# AirSensor_LoRA.net
KiCad netlist of a schematic drawn in EAGLE
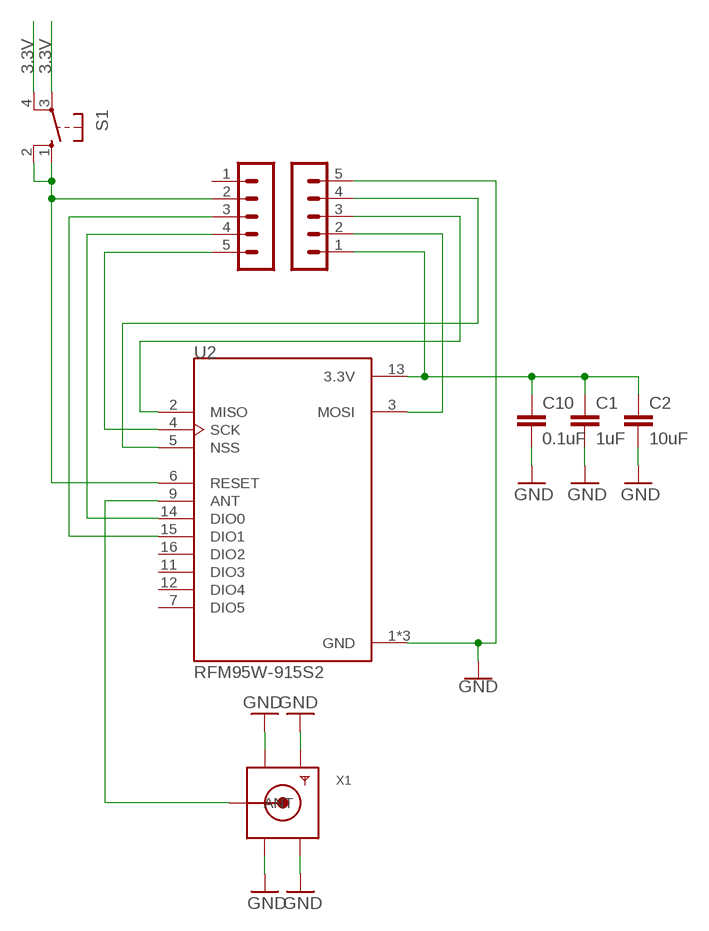
[diagram p0: schematic, sheet 1]

(export (version "E")
  (design (tool "Eeschema 10.0.6"))
  (components
    (comp (ref "C1")
      (value "1uF")
      (footprint "eagle-import:0805")
      (libsource (lib "eagle-import") (part "1.0UF-0805-25V-10%"))
    )
    (comp (ref "C2")
      (value "10uF")
      (footprint "eagle-import:0805")
      (libsource (lib "eagle-import") (part "1.0UF-0805-25V-10%"))
    )
    (comp (ref "C10")
      (value "0.1uF")
      (footprint "eagle-import:0805")
      (libsource (lib "eagle-import") (part "1.0UF-0805-25V-10%"))
    )
    (comp (ref "RFM95W_1")
      (value "LoRa_1")
      (footprint "eagle-import:MA05-1")
      (libsource (lib "eagle-import") (part "MA05-1"))
    )
    (comp (ref "RFM95W_2")
      (value "LoRa_2")
      (footprint "eagle-import:MA05-1")
      (libsource (lib "eagle-import") (part "MA05-1"))
    )
    (comp (ref "S1")
      (value "10-XX")
      (footprint "eagle-import:B3F-10XX")
      (fields (field (name "MPN") "B3F-1000"))
      (libsource (lib "eagle-import") (part "10-XX"))
    )
    (comp (ref "U2")
      (value "RFM95W-915S2")
      (footprint "eagle-import:XCVR_RFM95W-915S2")
      (fields (field (name "MF") "RF Solutions"))
      (libsource (lib "eagle-import") (part "RFM95W-915S2"))
    )
    (comp (ref "X1")
      (value "SMACONNECTOR_EDGE")
      (footprint "eagle-import:SMA_EDGELAUNCH")
      (libsource (lib "eagle-import") (part "SMACONNECTOR_EDGE"))
    )
  )
  (nets
    (net (code "1") (name "/3.3V") (class "Default")
      (node (ref "S1") (pin "3") (pinfunction "P_3") (pintype "passive"))
      (node (ref "S1") (pin "4") (pinfunction "P1_4") (pintype "passive"))
    )
    (net (code "2") (name "GND") (class "Default")
      (node (ref "C1") (pin "2") (pinfunction "2_2") (pintype "passive"))
      (node (ref "C10") (pin "2") (pinfunction "2_2") (pintype "passive"))
      (node (ref "C2") (pin "2") (pinfunction "2_2") (pintype "passive"))
      (node (ref "RFM95W_2") (pin "5") (pinfunction "5_5") (pintype "passive"))
      (node (ref "U2") (pin "1") (pinfunction "GND_1") (pintype "power_in"))
      (node (ref "U2") (pin "10") (pinfunction "GND_10") (pintype "power_in"))
      (node (ref "U2") (pin "8") (pinfunction "GND_8") (pintype "power_in"))
      (node (ref "X1") (pin "GND@1") (pinfunction "GND4_GND@1") (pintype "power_in"))
      (node (ref "X1") (pin "GND@2") (pinfunction "GND3_GND@2") (pintype "power_in"))
      (node (ref "X1") (pin "GND@3") (pinfunction "GND2_GND@3") (pintype "power_in"))
      (node (ref "X1") (pin "GND@4") (pinfunction "GND1_GND@4") (pintype "power_in"))
    )
    (net (code "3") (name "Net-(S1-S)") (class "Default")
      (node (ref "RFM95W_1") (pin "2") (pinfunction "2_2") (pintype "passive"))
      (node (ref "S1") (pin "1") (pinfunction "S_1") (pintype "passive"))
      (node (ref "S1") (pin "2") (pinfunction "S1_2") (pintype "passive"))
      (node (ref "U2") (pin "6") (pinfunction "RESET_6") (pintype "bidirectional"))
    )
    (net (code "4") (name "Net-(U2-3.3V)") (class "Default")
      (node (ref "C1") (pin "1") (pinfunction "1_1") (pintype "passive"))
      (node (ref "C10") (pin "1") (pinfunction "1_1") (pintype "passive"))
      (node (ref "C2") (pin "1") (pinfunction "1_1") (pintype "passive"))
      (node (ref "RFM95W_2") (pin "1") (pinfunction "1_1") (pintype "passive"))
      (node (ref "U2") (pin "13") (pinfunction "3.3V_13") (pintype "power_in"))
    )
    (net (code "5") (name "Net-(U2-ANT)") (class "Default")
      (node (ref "U2") (pin "9") (pinfunction "ANT_9") (pintype "bidirectional"))
      (node (ref "X1") (pin "P") (pinfunction "ANT_P") (pintype "bidirectional"))
    )
    (net (code "6") (name "Net-(U2-DIO0)") (class "Default")
      (node (ref "RFM95W_1") (pin "4") (pinfunction "4_4") (pintype "passive"))
      (node (ref "U2") (pin "14") (pinfunction "DIO0_14") (pintype "bidirectional"))
    )
    (net (code "7") (name "Net-(U2-DIO1)") (class "Default")
      (node (ref "RFM95W_1") (pin "3") (pinfunction "3_3") (pintype "passive"))
      (node (ref "U2") (pin "15") (pinfunction "DIO1_15") (pintype "bidirectional"))
    )
    (net (code "8") (name "Net-(U2-MISO)") (class "Default")
      (node (ref "RFM95W_2") (pin "3") (pinfunction "3_3") (pintype "passive"))
      (node (ref "U2") (pin "2") (pinfunction "MISO_2") (pintype "input"))
    )
    (net (code "9") (name "Net-(U2-MOSI)") (class "Default")
      (node (ref "RFM95W_2") (pin "2") (pinfunction "2_2") (pintype "passive"))
      (node (ref "U2") (pin "3") (pinfunction "MOSI_3") (pintype "output"))
    )
    (net (code "10") (name "Net-(U2-NSS)") (class "Default")
      (node (ref "RFM95W_2") (pin "4") (pinfunction "4_4") (pintype "passive"))
      (node (ref "U2") (pin "5") (pinfunction "NSS_5") (pintype "input"))
    )
    (net (code "11") (name "Net-(U2-SCK)") (class "Default")
      (node (ref "RFM95W_1") (pin "5") (pinfunction "5_5") (pintype "passive"))
      (node (ref "U2") (pin "4") (pinfunction "SCK_4") (pintype "input"))
    )
    (net (code "12") (name "unconnected-(RFM95W_1-Pad1)") (class "Default")
      (node (ref "RFM95W_1") (pin "1") (pinfunction "1_1") (pintype "passive"))
    )
    (net (code "13") (name "unconnected-(U2-DIO2-Pad16)") (class "Default")
      (node (ref "U2") (pin "16") (pinfunction "DIO2_16") (pintype "bidirectional"))
    )
    (net (code "14") (name "unconnected-(U2-DIO3-Pad11)") (class "Default")
      (node (ref "U2") (pin "11") (pinfunction "DIO3_11") (pintype "bidirectional"))
    )
    (net (code "15") (name "unconnected-(U2-DIO4-Pad12)") (class "Default")
      (node (ref "U2") (pin "12") (pinfunction "DIO4_12") (pintype "bidirectional"))
    )
    (net (code "16") (name "unconnected-(U2-DIO5-Pad7)") (class "Default")
      (node (ref "U2") (pin "7") (pinfunction "DIO5_7") (pintype "bidirectional"))
    )
  )
)
